# Jason_BlinkyB.net
KiCad netlist of a schematic drawn in EAGLE
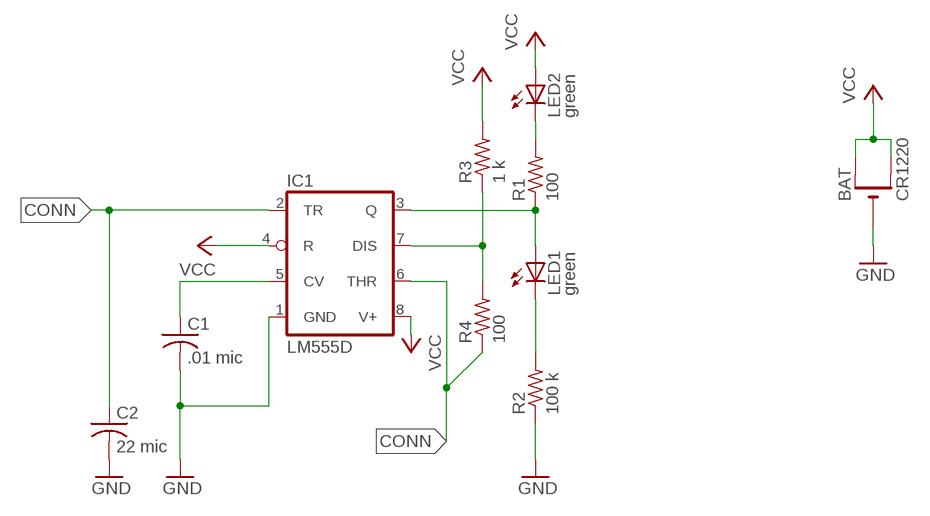
[diagram p0: schematic, sheet 1]

(export (version "E")
  (design (tool "Eeschema 10.0.6"))
  (components
    (comp (ref "BAT")
      (value "CR1220")
      (footprint "eagle-import:CR1220-SMD")
      (fields (field (name "MPN") "3080"))
      (libsource (lib "eagle-import") (part "CR1220SMT"))
    )
    (comp (ref "C1")
      (value ".01 mic")
      (footprint "eagle-import:C0805")
      (fields (field (name "MF") "KEMET") (field (name "MPN") "C0805C103K5RACTU"))
      (libsource (lib "eagle-import") (part "C-USC0805"))
    )
    (comp (ref "C2")
      (value "22 mic")
      (footprint "eagle-import:C0805")
      (fields (field (name "MPN") "TL8W9226M010C"))
      (libsource (lib "eagle-import") (part "C-USC0805"))
    )
    (comp (ref "IC1")
      (value "LM555D")
      (footprint "eagle-import:SO08")
      (fields (field (name "MPN") "TLC555CD."))
      (libsource (lib "eagle-import") (part "555DLM"))
    )
    (comp (ref "LED1")
      (value "green")
      (footprint "eagle-import:CHIPLED_0805")
      (fields (field (name "MPN") "150080GS75000"))
      (libsource (lib "eagle-import") (part "LEDCHIPLED_0805"))
    )
    (comp (ref "LED2")
      (value "green")
      (footprint "eagle-import:CHIPLED_0805")
      (fields (field (name "MPN") "150080GS75000"))
      (libsource (lib "eagle-import") (part "LEDCHIPLED_0805"))
    )
    (comp (ref "R1")
      (value "100")
      (footprint "eagle-import:R0805")
      (fields (field (name "MPN") "CR0805-JW-101ELF"))
      (libsource (lib "eagle-import") (part "R-US_R0805"))
    )
    (comp (ref "R2")
      (value "100 k")
      (footprint "eagle-import:R0805")
      (fields (field (name "MF") "FARNELL") (field (name "MPN") "MC01W08055100K"))
      (libsource (lib "eagle-import") (part "R-US_R0805"))
    )
    (comp (ref "R3")
      (value "1 k")
      (footprint "eagle-import:R0805")
      (fields (field (name "MF") "VISHAY/DALE") (field (name "MPN") "CRCW08051K00FKTA"))
      (libsource (lib "eagle-import") (part "R-US_R0805"))
    )
    (comp (ref "R4")
      (value "100")
      (footprint "eagle-import:R0805")
      (fields (field (name "MPN") "CR0805-JW-101ELF"))
      (libsource (lib "eagle-import") (part "R-US_R0805"))
    )
  )
  (nets
    (net (code "1") (name "CONN") (class "Default")
      (node (ref "C2") (pin "1") (pinfunction "1_1") (pintype "passive"))
      (node (ref "IC1") (pin "2") (pinfunction "TR_2") (pintype "input"))
      (node (ref "IC1") (pin "6") (pinfunction "THR_6") (pintype "input"))
      (node (ref "R4") (pin "1") (pinfunction "1_1") (pintype "passive"))
    )
    (net (code "2") (name "GND") (class "Default")
      (node (ref "BAT") (pin "-") (pinfunction "-_-") (pintype "passive"))
      (node (ref "C1") (pin "2") (pinfunction "2_2") (pintype "passive"))
      (node (ref "C2") (pin "2") (pinfunction "2_2") (pintype "passive"))
      (node (ref "IC1") (pin "1") (pinfunction "GND_1") (pintype "power_in"))
      (node (ref "R2") (pin "1") (pinfunction "1_1") (pintype "passive"))
    )
    (net (code "3") (name "Net-(IC1-CV)") (class "Default")
      (node (ref "C1") (pin "1") (pinfunction "1_1") (pintype "passive"))
      (node (ref "IC1") (pin "5") (pinfunction "CV_5") (pintype "input"))
    )
    (net (code "4") (name "Net-(IC1-DIS)") (class "Default")
      (node (ref "IC1") (pin "7") (pinfunction "DIS_7") (pintype "input"))
      (node (ref "R3") (pin "1") (pinfunction "1_1") (pintype "passive"))
      (node (ref "R4") (pin "2") (pinfunction "2_2") (pintype "passive"))
    )
    (net (code "5") (name "Net-(IC1-Q)") (class "Default")
      (node (ref "IC1") (pin "3") (pinfunction "Q_3") (pintype "output"))
      (node (ref "LED1") (pin "A") (pinfunction "A_A") (pintype "passive"))
      (node (ref "R1") (pin "1") (pinfunction "1_1") (pintype "passive"))
    )
    (net (code "6") (name "Net-(LED1-PadC)") (class "Default")
      (node (ref "LED1") (pin "C") (pinfunction "C_C") (pintype "passive"))
      (node (ref "R2") (pin "2") (pinfunction "2_2") (pintype "passive"))
    )
    (net (code "7") (name "Net-(LED2-PadC)") (class "Default")
      (node (ref "LED2") (pin "C") (pinfunction "C_C") (pintype "passive"))
      (node (ref "R1") (pin "2") (pinfunction "2_2") (pintype "passive"))
    )
    (net (code "8") (name "VCC") (class "Default")
      (node (ref "BAT") (pin "+$1") (pinfunction "+_+$1") (pintype "passive"))
      (node (ref "BAT") (pin "+$2") (pinfunction "+1_+$2") (pintype "passive"))
      (node (ref "IC1") (pin "4") (pinfunction "R_4") (pintype "input"))
      (node (ref "IC1") (pin "8") (pinfunction "V+_8") (pintype "power_in"))
      (node (ref "LED2") (pin "A") (pinfunction "A_A") (pintype "passive"))
      (node (ref "R3") (pin "2") (pinfunction "2_2") (pintype "passive"))
    )
  )
)
